# WX0_011_104DL.net
KiCad netlist of a schematic drawn in Altium Designer
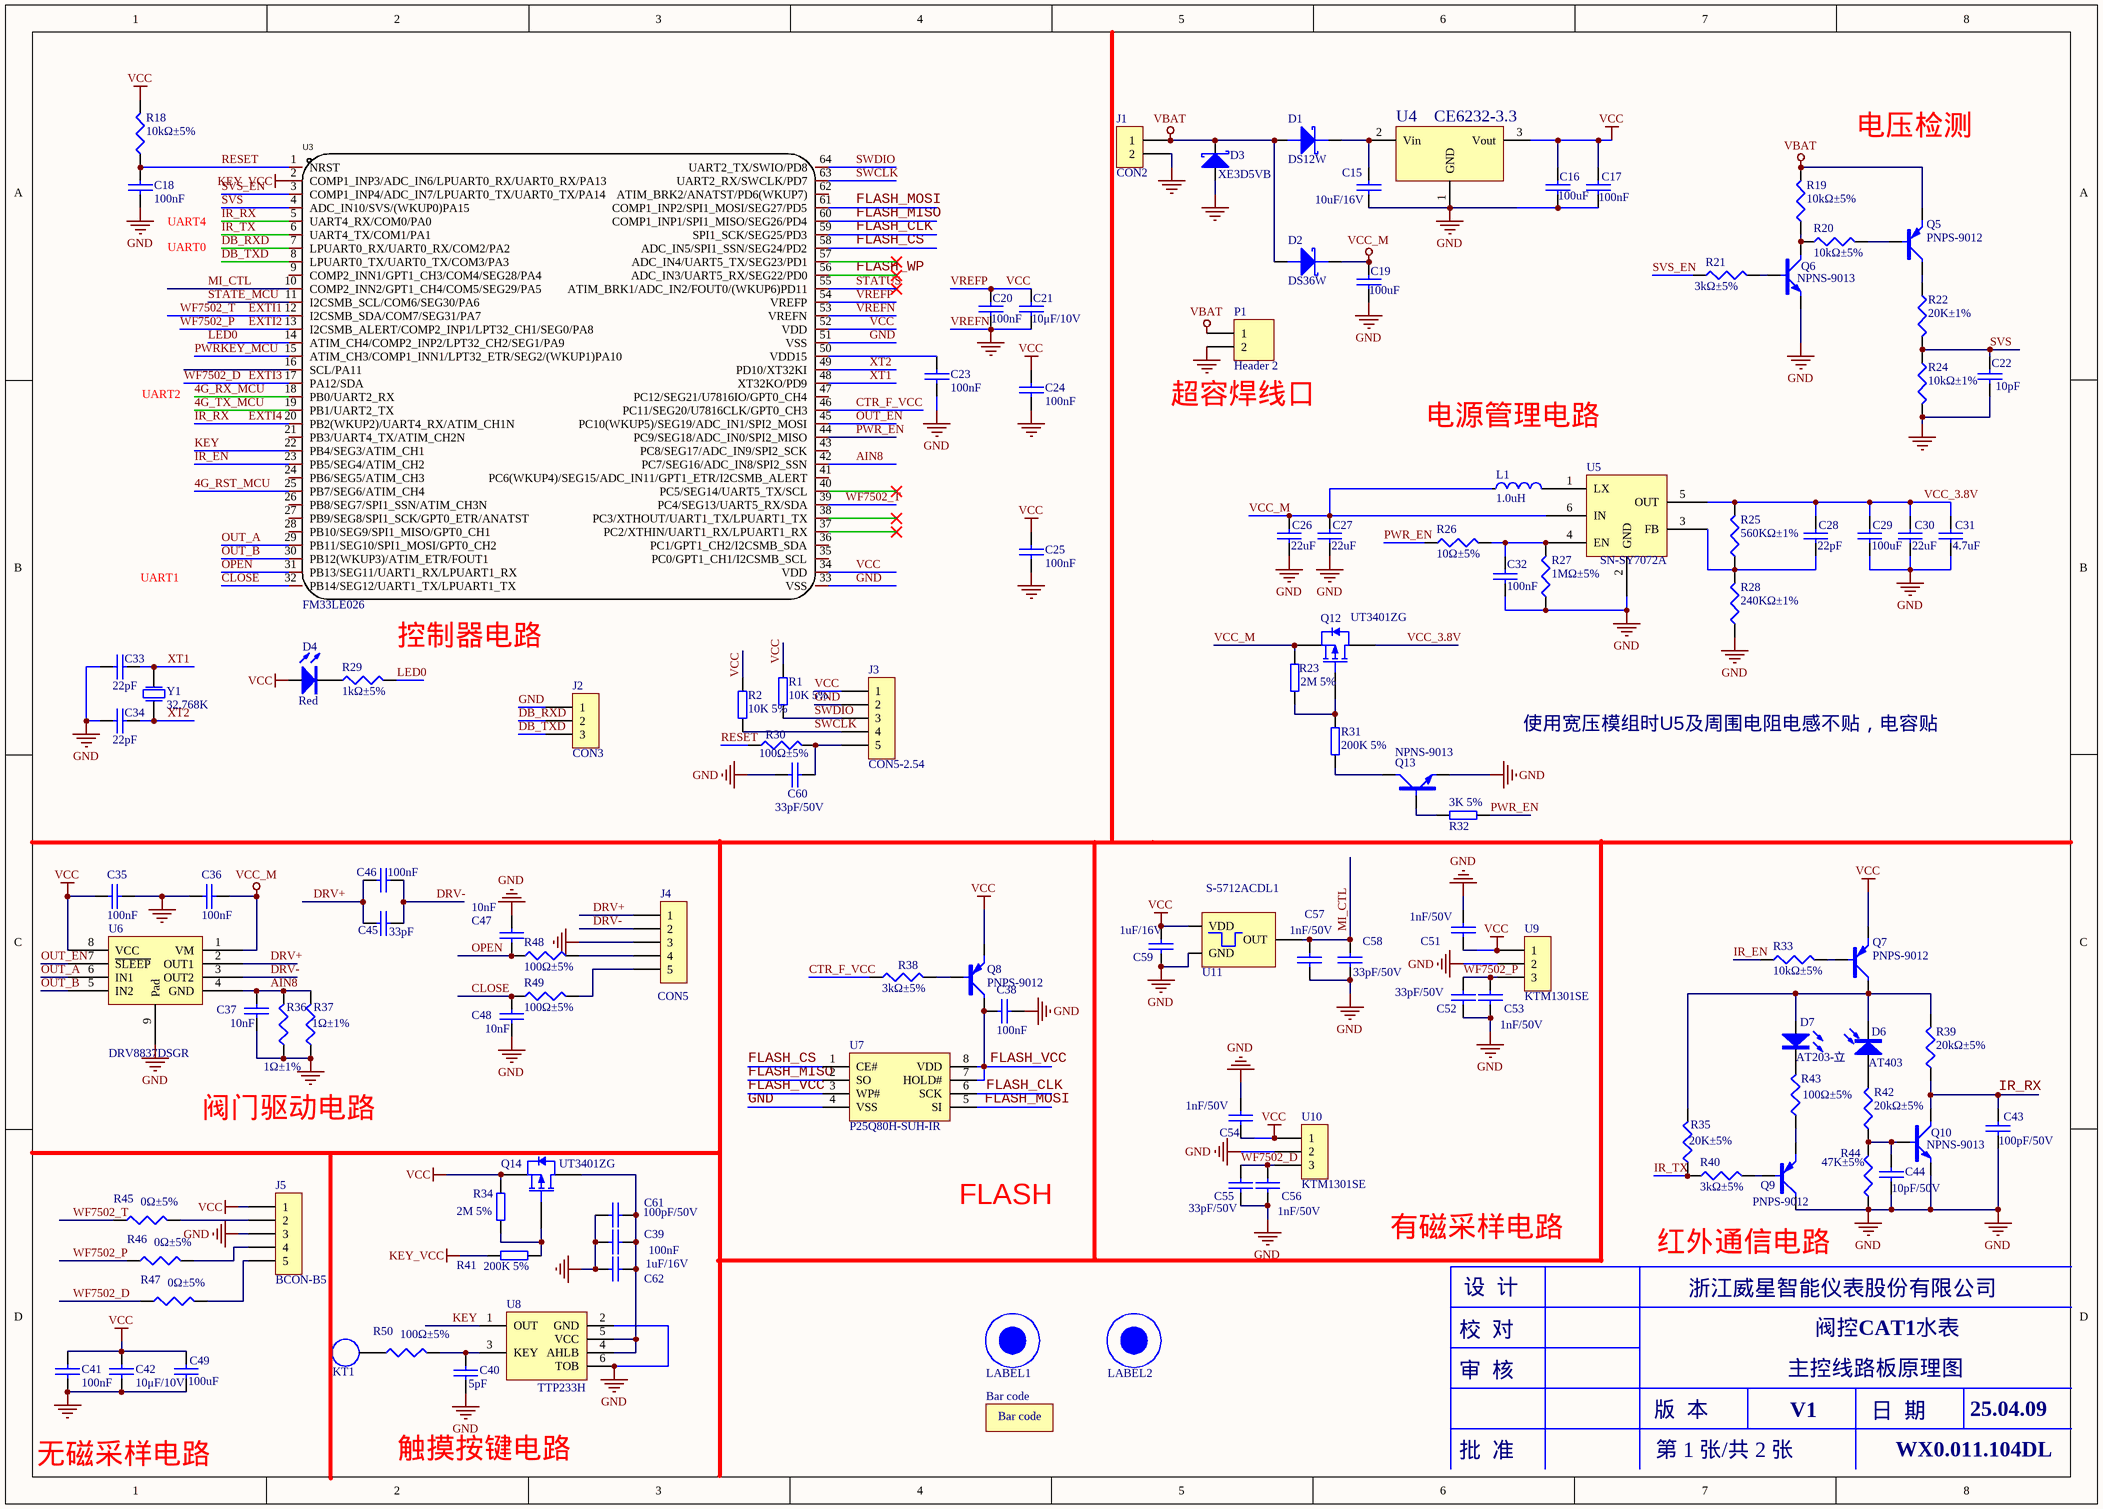
[diagram p0: WX0.011.104DL.SchDoc]

(export (version "E")
  (design (tool "Eeschema 10.0.6"))
  (components
    (comp (ref "Bar code")
      (value "Bar code")
      (footprint "Bar Code1")
      (libsource (lib "Connect_WX") (part "txm"))
    )
    (comp (ref "C15")
      (value "10uF/16V")
      (footprint "CAP0603")
      (description "105pF,16V,±10%,0603,国巨,CC0603KRX7R7BB105")
      (fields (field (name "PART NUMBER") "101020103-0003"))
      (libsource (lib "海外直通表U-GR3_GPRS") (part "CC03K7R7_1uF"))
    )
    (comp (ref "C16")
      (value "100uF")
      (footprint "GRM1206")
      (description "贴片电容,100uF±20%/6.3V,X5R,村田")
      (fields (field (name "PART NUMBER") "101020101-0020") (field (name "MANUFACTURER") "村田"))
      (libsource (lib "Devices") (part "CAP"))
    )
    (comp (ref "C17")
      (value "100nF")
      (footprint "CAP0603")
      (description "贴片电容,100nF±10%/50V,X7R,国巨")
      (fields (field (name "PART NUMBER") "101020103-0021") (field (name "MANUFACTURER") "国巨"))
      (libsource (lib "Devices") (part "CAP"))
    )
    (comp (ref "C18")
      (value "100nF")
      (footprint "CAP0603")
      (description "贴片电容,100nF±10%/50V,X7R,国巨")
      (fields (field (name "PART NUMBER") "101020103-0021") (field (name "MANUFACTURER") "国巨"))
      (libsource (lib "Devices") (part "CAP"))
    )
    (comp (ref "C19")
      (value "100uF")
      (footprint "GRM1206")
      (description "贴片电容,100uF±20%/6.3V,X5R,村田")
      (fields (field (name "PART NUMBER") "101020101-0020") (field (name "MANUFACTURER") "村田"))
      (libsource (lib "Devices") (part "CAP"))
    )
    (comp (ref "C20")
      (value "100nF")
      (footprint "CAP0603")
      (description "贴片电容,100nF±10%/50V,X7R,国巨")
      (fields (field (name "PART NUMBER") "101020103-0021") (field (name "MANUFACTURER") "国巨"))
      (libsource (lib "Devices") (part "CAP"))
    )
    (comp (ref "C21")
      (value "10μF/10V")
      (footprint "CAP0603")
      (description "贴片电容,10μF±10%/10V,X7R,村田")
      (fields (field (name "PART NUMBER") "101020103-0026") (field (name "MANUFACTURER") "村田"))
      (libsource (lib "Devices") (part "CAP"))
    )
    (comp (ref "C22")
      (value "10pF")
      (footprint "CAP0603")
      (description "贴片电容,12pF±5%/50V,NPO,国巨")
      (fields (field (name "PART NUMBER") "101020103-0005") (field (name "MANUFACTURER") "国巨"))
      (libsource (lib "Devices") (part "CAP"))
    )
    (comp (ref "C23")
      (value "100nF")
      (footprint "CAP0603")
      (description "贴片电容,100nF±10%/50V,X7R,国巨")
      (fields (field (name "PART NUMBER") "101020103-0021") (field (name "MANUFACTURER") "国巨"))
      (libsource (lib "Devices") (part "CAP"))
    )
    (comp (ref "C24")
      (value "100nF")
      (footprint "CAP0603")
      (description "贴片电容,100nF±10%/50V,X7R,国巨")
      (fields (field (name "PART NUMBER") "101020103-0021") (field (name "MANUFACTURER") "国巨"))
      (libsource (lib "Devices") (part "CAP"))
    )
    (comp (ref "C25")
      (value "100nF")
      (footprint "CAP0603")
      (description "贴片电容,100nF±10%/50V,X7R,国巨")
      (fields (field (name "PART NUMBER") "101020103-0021") (field (name "MANUFACTURER") "国巨"))
      (libsource (lib "Devices") (part "CAP"))
    )
    (comp (ref "C26")
      (value "22uF")
      (footprint "CAP0603")
      (description "贴片电容,22uF±20%,10V,X5R,村田")
      (fields (field (name "PART NUMBER") "101020103-0037") (field (name "MANUFACTURER") "村田"))
      (libsource (lib "Devices") (part "CAP"))
    )
    (comp (ref "C27")
      (value "22uF")
      (footprint "CAP0603")
      (description "贴片电容,22uF±20%,10V,X5R,村田")
      (fields (field (name "PART NUMBER") "101020103-0037") (field (name "MANUFACTURER") "村田"))
      (libsource (lib "Devices") (part "CAP"))
    )
    (comp (ref "C28")
      (value "22pF")
      (footprint "CAP0603")
      (description "贴片电容,22pF±5%/50V,NP0,国巨")
      (fields (field (name "PART NUMBER") "101020103-0009") (field (name "MANUFACTURER") "国巨"))
      (libsource (lib "Devices") (part "CAP"))
    )
    (comp (ref "C29")
      (value "100uF")
      (footprint "GRM1206")
      (description "贴片电容,100uF±20%/6.3V,X5R,村田")
      (fields (field (name "PART NUMBER") "101020101-0020") (field (name "MANUFACTURER") "村田"))
      (libsource (lib "Devices") (part "CAP"))
    )
    (comp (ref "C30")
      (value "22uF")
      (footprint "CAP0603")
      (description "贴片电容,22uF±20%,10V,X5R,村田")
      (fields (field (name "PART NUMBER") "101020103-0037") (field (name "MANUFACTURER") "村田"))
      (libsource (lib "Devices") (part "CAP"))
    )
    (comp (ref "C31")
      (value "4.7uF")
      (footprint "CAP0603")
      (description "贴片电容,4.7uF±10%/35V,X5R,村田")
      (fields (field (name "PART NUMBER") "101020103-0036") (field (name "MANUFACTURER") "村田"))
      (libsource (lib "Devices") (part "CAP"))
    )
    (comp (ref "C32")
      (value "100nF")
      (footprint "CAP0603")
      (description "贴片电容,100nF±10%/50V,X7R,国巨")
      (fields (field (name "PART NUMBER") "101020103-0021") (field (name "MANUFACTURER") "国巨"))
      (libsource (lib "Devices") (part "CAP"))
    )
    (comp (ref "C33")
      (value "22pF")
      (footprint "CAP0603")
      (description "贴片电容,22pF±5%/50V,NP0,国巨")
      (fields (field (name "PART NUMBER") "101020103-0009") (field (name "MANUFACTURER") "国巨"))
      (libsource (lib "Devices") (part "CAP"))
    )
    (comp (ref "C34")
      (value "22pF")
      (footprint "CAP0603")
      (description "贴片电容,22pF±5%/50V,NP0,国巨")
      (fields (field (name "PART NUMBER") "101020103-0009") (field (name "MANUFACTURER") "国巨"))
      (libsource (lib "Devices") (part "CAP"))
    )
    (comp (ref "C35")
      (value "100nF")
      (footprint "CAP0603")
      (description "贴片电容,100nF±10%/50V,X7R,国巨")
      (fields (field (name "PART NUMBER") "101020103-0021") (field (name "MANUFACTURER") "国巨"))
      (libsource (lib "Devices") (part "CAP"))
    )
    (comp (ref "C36")
      (value "100nF")
      (footprint "CAP0603")
      (description "贴片电容,100nF±10%/50V,X7R,国巨")
      (fields (field (name "PART NUMBER") "101020103-0021") (field (name "MANUFACTURER") "国巨"))
      (libsource (lib "Devices") (part "CAP"))
    )
    (comp (ref "C37")
      (value "10nF")
      (footprint "CAP0603")
      (description "贴片电容,10nF±10%/50V,X7R,国巨")
      (fields (field (name "PART NUMBER") "101020103-0007") (field (name "MANUFACTURER") "国巨"))
      (libsource (lib "Devices") (part "CAP"))
    )
    (comp (ref "C38")
      (value "100nF")
      (footprint "CAP0603")
      (description "贴片电容,100nF±10%/50V,X7R,国巨")
      (fields (field (name "PART NUMBER") "101020103-0021") (field (name "MANUFACTURER") "国巨"))
      (libsource (lib "Devices") (part "CAP"))
    )
    (comp (ref "C39")
      (value "100nF")
      (footprint "CAP0603")
      (description "贴片电容,100nF±10%/50V,X7R,国巨")
      (fields (field (name "PART NUMBER") "101020103-0021") (field (name "MANUFACTURER") "国巨"))
      (libsource (lib "Devices") (part "CAP"))
    )
    (comp (ref "C40")
      (value "5pF")
      (footprint "CAP0603")
      (description "贴片电容,4.7pF±0.25pF/50V,NPO,国巨")
      (fields (field (name "PART NUMBER") "101020103-0040") (field (name "MANUFACTURER") "国巨"))
      (libsource (lib "Devices") (part "CAP"))
    )
    (comp (ref "C41")
      (value "100nF")
      (footprint "CAP0603")
      (description "贴片电容,100nF±10%/50V,X7R,国巨")
      (fields (field (name "PART NUMBER") "101020103-0021") (field (name "MANUFACTURER") "国巨"))
      (libsource (lib "Devices") (part "CAP"))
    )
    (comp (ref "C42")
      (value "10μF/10V")
      (footprint "CAP0603")
      (description "贴片电容,1μF±10%/16V,X7R,国巨")
      (fields (field (name "PART NUMBER") "101020103-0003") (field (name "MANUFACTURER") "国巨"))
      (libsource (lib "Devices") (part "CAP"))
    )
    (comp (ref "C43")
      (value "100pF/50V")
      (footprint "CAP0603")
      (description "101pf,50 V,±5%,0603,国巨,CC0603JRNP09BN101")
      (fields (field (name "PART NUMBER") "101020103-0010"))
      (libsource (lib "Database_Libs2") (part "CC03JPO9_101P"))
    )
    (comp (ref "C44")
      (value "10pF/50V")
      (footprint "CAP0603")
      (description "10pF,50 V,±5%,0603,X7R,国巨,CC0603JRNPO9BN100")
      (fields (field (name "PART NUMBER") "101020103-0014"))
      (libsource (lib "Database_Libs2") (part "CC03JPO9_10P"))
    )
    (comp (ref "C45")
      (value "33pF")
      (footprint "CAP0603")
      (description "贴片电容,100nF±10%/50V,X7R,国巨")
      (fields (field (name "PART NUMBER") "101020103-0021") (field (name "MANUFACTURER") "国巨"))
      (libsource (lib "Devices") (part "CAP"))
    )
    (comp (ref "C46")
      (value "100nF")
      (footprint "CAP0603")
      (description "贴片电容,100nF±10%/50V,X7R,国巨")
      (fields (field (name "PART NUMBER") "101020103-0021") (field (name "MANUFACTURER") "国巨"))
      (libsource (lib "Devices") (part "CAP"))
    )
    (comp (ref "C47")
      (value "10nF")
      (footprint "CAP0603")
      (description "贴片电容,10nF±10%/50V,X7R,国巨")
      (fields (field (name "PART NUMBER") "101020103-0007") (field (name "MANUFACTURER") "国巨"))
      (libsource (lib "Devices") (part "CAP"))
    )
    (comp (ref "C48")
      (value "10nF")
      (footprint "CAP0603")
      (description "贴片电容,10nF±10%/50V,X7R,国巨")
      (fields (field (name "PART NUMBER") "101020103-0007") (field (name "MANUFACTURER") "国巨"))
      (libsource (lib "Devices") (part "CAP"))
    )
    (comp (ref "C49")
      (value "100uF")
      (footprint "GRM1206")
      (description "贴片电容,100uF±20%/6.3V,X5R,村田")
      (fields (field (name "PART NUMBER") "101020101-0020") (field (name "MANUFACTURER") "村田"))
      (libsource (lib "Devices") (part "CAP"))
    )
    (comp (ref "C51")
      (value "1nF/50V")
      (footprint "CAP0603")
      (description "102pF,50 V,±10%,0603,国巨,CC0603KRX7R9BB102")
      (fields (field (name "PART NUMBER") "101020103-0022"))
      (libsource (lib "Database_Libs2") (part "CC03K7R9_1N"))
    )
    (comp (ref "C52")
      (value "33pF/50V")
      (footprint "CAP0603")
      (description "33pF,50 V,±10%,0603,国巨,CC0603KRNPO9BN33")
      (fields (field (name "PART NUMBER") "101020103-0027"))
      (libsource (lib "Database_Libs2") (part "CC03KPO9_33P"))
    )
    (comp (ref "C53")
      (value "1nF/50V")
      (footprint "CAP0603")
      (description "102pF,50 V,±10%,0603,国巨,CC0603KRX7R9BB102")
      (fields (field (name "PART NUMBER") "101020103-0022"))
      (libsource (lib "Database_Libs2") (part "CC03K7R9_1N"))
    )
    (comp (ref "C54")
      (value "1nF/50V")
      (footprint "CAP0603")
      (description "102pF,50 V,±10%,0603,国巨,CC0603KRX7R9BB102")
      (fields (field (name "PART NUMBER") "101020103-0022"))
      (libsource (lib "Database_Libs2") (part "CC03K7R9_1N"))
    )
    (comp (ref "C55")
      (value "33pF/50V")
      (footprint "CAP0603")
      (description "33pF,50 V,±10%,0603,国巨,CC0603KRNPO9BN33")
      (fields (field (name "PART NUMBER") "101020103-0027"))
      (libsource (lib "Database_Libs2") (part "CC03KPO9_33P"))
    )
    (comp (ref "C56")
      (value "1nF/50V")
      (footprint "CAP0603")
      (description "102pF,50 V,±10%,0603,国巨,CC0603KRX7R9BB102")
      (fields (field (name "PART NUMBER") "101020103-0022"))
      (libsource (lib "Database_Libs2") (part "CC03K7R9_1N"))
    )
    (comp (ref "C57")
      (value "1nF/50V")
      (footprint "CAP0603")
      (description "102pF,50 V,±10%,0603,国巨,CC0603KRX7R9BB102")
      (fields (field (name "PART NUMBER") "101020103-0022"))
      (libsource (lib "Database_Libs2") (part "CC03K7R9_1N"))
    )
    (comp (ref "C58")
      (value "33pF/50V")
      (footprint "CAP0603")
      (description "33pF,50 V,±10%,0603,国巨,CC0603KRNPO9BN33")
      (fields (field (name "PART NUMBER") "101020103-0027"))
      (libsource (lib "Database_Libs2") (part "CC03KPO9_33P"))
    )
    (comp (ref "C59")
      (value "1uF/16V")
      (footprint "CAP0603")
      (description "105pF,16 V,±10%,0603,国巨,CC0603KRX7R7BB105")
      (fields (field (name "PART NUMBER") "101020103-0003"))
      (libsource (lib "Database_Libs2") (part "CC03K7R7_1U"))
    )
    (comp (ref "C60")
      (value "33pF/50V")
      (footprint "CAP0603")
      (description "33pF,50 V,±10%,0603,国巨,CC0603KRNPO9BN33")
      (fields (field (name "PART NUMBER") "101020103-0027"))
      (libsource (lib "Database_Libs2") (part "CC03KPO9_33P"))
    )
    (comp (ref "C61")
      (value "100pF/50V")
      (footprint "CAP0603")
      (description "101pf,50 V,±5%,0603,国巨,CC0603JRNP09BN101")
      (fields (field (name "PART NUMBER") "101020103-0010"))
      (libsource (lib "Database_Libs2") (part "CC03JPO9_101P"))
    )
    (comp (ref "C62")
      (value "1uF/16V")
      (footprint "CAP0603")
      (description "105pF,16 V,±10%,0603,国巨,CC0603KRX7R7BB105")
      (fields (field (name "PART NUMBER") "101020103-0003"))
      (libsource (lib "Database_Libs2") (part "CC03K7R7_1U"))
    )
    (comp (ref "D1")
      (value "DS12W")
      (footprint "SOD-123FL")
      (description "DS36W,SOD123-FL,3 A,42 V,60 V,浙江领晨科技有限公司,DS36W")
      (fields (field (name "PART NUMBER") "101040101-0055"))
      (libsource (lib "Database_Libs2") (part "02_DS36W"))
    )
    (comp (ref "D2")
      (value "DS36W")
      (footprint "SOD-123FL")
      (description "DS36W,SOD123-FL,3 A,42 V,60 V,浙江领晨科技有限公司,DS36W")
      (fields (field (name "PART NUMBER") "101040101-0055"))
      (libsource (lib "Database_Libs2") (part "02_DS36W"))
    )
    (comp (ref "D3")
      (value "XE3D5VB")
      (footprint "SOD-323_L1.8-W1.3-LS2.5-RD")
      (description "具有3.5pF低结电容，适用于IO线、电源线、高速信号的ESD二极管阵列,SOD-323,5 V,5 V,350 W,5 A,1 uA,矽航,XE3D5VB")
      (fields (field (name "PART NUMBER") "101040104-0010") (field (name "MANUFACTURER") "矽航"))
      (libsource (lib "Devices") (part "DIODE1"))
    )
    (comp (ref "D4")
      (value "Red")
      (footprint "LED-0603")
      (description "发光二极管,红色,0603,光宝")
      (fields (field (name "PART NUMBER") "101040102-0006") (field (name "MANUFACTURER") "光宝"))
      (libsource (lib "") (part "LED_1"))
    )
    (comp (ref "D6")
      (value "AT403")
      (footprint "LED2_300")
      (description "红外接收头，插件，红光，AT403_PD_01")
      (fields (field (name "PART NUMBER") "101040102-0011") (field (name "MANUFACTURER") "品观"))
      (libsource (lib "Devices") (part "LED_IN"))
    )
    (comp (ref "D7")
      (value "AT203-立")
      (footprint "LED2_300")
      (description "红外发射头，插件，红光，AT203")
      (fields (field (name "PART NUMBER") "101040102-0010") (field (name "MANUFACTURER") "品观"))
      (libsource (lib "Devices") (part "LED"))
    )
    (comp (ref "J1")
      (value "CON2")
      (footprint "SIP-2")
      (description "焊接插座,间距2.54mm")
      (libsource (lib "Devices") (part "CON2"))
    )
    (comp (ref "J2")
      (value "CON3")
      (footprint "SIP-3")
      (description "焊接插座,间距2.54mm")
      (libsource (lib "Devices") (part "CON3"))
    )
    (comp (ref "J3")
      (value "CON5-2.54")
      (footprint "PIN254_1*5*1100S")
      (description "焊接插座,间距2.0mm")
      (libsource (lib "Devices") (part "CON5"))
    )
    (comp (ref "J4")
      (value "CON5")
      (footprint "PIN254_1*5*1100S")
      (description "焊接插座,间距2.54mm")
      (libsource (lib "Devices") (part "CON5"))
    )
    (comp (ref "J5")
      (value "BCON-B5")
      (footprint "J_DIP_2.0_1*05_H")
      (description "焊接插座,90度插板双面焊盘,公头,间距1.5mm")
      (libsource (lib "Devices") (part "CON5"))
    )
    (comp (ref "KT1")
      (value "Touch")
      (footprint "TOUCH-1")
      (description "按键,6mm弹簧按键,按键直径10mm")
      (fields (field (name "PART NUMBER") "1011001-0060"))
      (libsource (lib "Devices") (part "TOUCHKEY"))
    )
    (comp (ref "L1")
      (value "1.0uH")
      (footprint "IND-SMD_L3.0-W3.0")
      (description "电感，1.0uH,2.7A,±20%,3.3*1.5mm，74438335010，伍尔特电子有限公司")
      (fields (field (name "PART NUMBER") "1010302-0019"))
      (libsource (lib "Devices") (part "L"))
    )
    (comp (ref "LABEL1")
      (value "~")
      (footprint "MARK")
      (description "标准Mark点,直径1mm,阻焊开窗3mm")
      (libsource (lib "Devices") (part "MARK"))
    )
    (comp (ref "LABEL2")
      (value "~")
      (footprint "MARK")
      (description "标准Mark点,直径1mm,阻焊开窗3mm")
      (libsource (lib "Devices") (part "MARK"))
    )
    (comp (ref "P1") (value "Header 2") (footprint "SIP-2") (libsource (lib "Connect_WX") (part "Header 2")))
    (comp (ref "Q5")
      (value "PNPS-9012")
      (footprint "SOT-23")
      (description "9012,PNP,SOT-23,JCET;长电,S9012")
      (fields (field (name "PART NUMBER") "101040201-0001"))
      (libsource (lib "Database_Libs2") (part "03_PNPS-9012"))
    )
    (comp (ref "Q6")
      (value "NPNS-9013")
      (footprint "SOT-23")
      (description "9013,NPN,SOT-23,长电,S9013")
      (fields (field (name "PART NUMBER") "101040201-0002"))
      (libsource (lib "Database_Libs2") (part "03_NPNS-9013"))
    )
    (comp (ref "Q7")
      (value "PNPS-9012")
      (footprint "SOT-23")
      (description "9012,PNP,SOT-23,JCET;长电,S9012")
      (fields (field (name "PART NUMBER") "101040201-0001"))
      (libsource (lib "Database_Libs2") (part "03_PNPS-9012"))
    )
    (comp (ref "Q8")
      (value "PNPS-9012")
      (footprint "SOT-23")
      (description "9012,PNP,SOT-23,JCET;长电,S9012")
      (fields (field (name "PART NUMBER") "101040201-0001"))
      (libsource (lib "Database_Libs2") (part "03_PNPS-9012"))
    )
    (comp (ref "Q9")
      (value "PNPS-9012")
      (footprint "SOT-23")
      (description "9012,PNP,SOT-23,JCET;长电,S9012")
      (fields (field (name "PART NUMBER") "101040201-0001"))
      (libsource (lib "Database_Libs2") (part "03_PNPS-9012"))
    )
    (comp (ref "Q10")
      (value "NPNS-9013")
      (footprint "SOT-23")
      (description "9013,NPN,SOT-23,长电,S9013")
      (fields (field (name "PART NUMBER") "101040201-0002"))
      (libsource (lib "Database_Libs2") (part "03_NPNS-9013"))
    )
    (comp (ref "Q12")
      (value "UT3401ZG")
      (footprint "SOT-23")
      (description "UT3401ZG,P-MOS,SOT-23,UTC,UT3401ZG")
      (fields (field (name "PART NUMBER") "101040201-0013"))
      (libsource (lib "Database_Libs2") (part "03_P-UT3401ZG"))
    )
    (comp (ref "Q13")
      (value "NPNS-9013")
      (footprint "SOT-23")
      (description "9013,NPN,SOT-23,长电,S9013")
      (fields (field (name "PART NUMBER") "101040201-0002"))
      (libsource (lib "Database_Libs2") (part "03_NPNS-9013"))
    )
    (comp (ref "Q14")
      (value "UT3401ZG")
      (footprint "SOT-23")
      (description "UT3401ZG,P-MOS,SOT-23,UTC,UT3401ZG")
      (fields (field (name "PART NUMBER") "101040201-0013"))
      (libsource (lib "Database_Libs2") (part "03_P-UT3401ZG"))
    )
    (comp (ref "R1")
      (value "10K 5%")
      (footprint "RES0603")
      (description "国巨,±5%,0603,,155 ℃,-55 ℃,RC0603JR-0710KL,无铅,200 ppm/℃,1/10W,,10K")
      (fields (field (name "PART NUMBER") "101010103-0003"))
      (libsource (lib "Database_Libs2") (part "RC03J_10K"))
    )
    (comp (ref "R2")
      (value "10K 5%")
      (footprint "RES0603")
      (description "国巨,±5%,0603,,155 ℃,-55 ℃,RC0603JR-0710KL,无铅,200 ppm/℃,1/10W,,10K")
      (fields (field (name "PART NUMBER") "101010103-0003"))
      (libsource (lib "Database_Libs2") (part "RC03J_10K"))
    )
    (comp (ref "R18")
      (value "10kΩ±5%")
      (footprint "RES0603")
      (description "贴片电阻,10kΩ±5%,1/10W,100ppm/℃,国巨")
      (fields (field (name "PART NUMBER") "101010103-0003") (field (name "MANUFACTURER") "国巨"))
      (libsource (lib "Devices") (part "RES1"))
    )
    (comp (ref "R19")
      (value "10kΩ±5%")
      (footprint "RES0603")
      (description "贴片电阻,10kΩ±5%,1/10W,100ppm/℃,国巨")
      (fields (field (name "PART NUMBER") "101010103-0003") (field (name "MANUFACTURER") "国巨"))
      (libsource (lib "Devices") (part "RES1"))
    )
    (comp (ref "R20")
      (value "10kΩ±5%")
      (footprint "RES0603")
      (description "贴片电阻,10kΩ±5%,1/10W,100ppm/℃,国巨")
      (fields (field (name "PART NUMBER") "101010103-0003") (field (name "MANUFACTURER") "国巨"))
      (libsource (lib "Devices") (part "RES1"))
    )
    (comp (ref "R21")
      (value "3kΩ±5%")
      (footprint "RES0603")
      (description "贴片电阻,4.7kΩ±5%,1/10W,100ppm/℃,国巨")
      (fields (field (name "PART NUMBER") "101010103-0042") (field (name "MANUFACTURER") "国巨"))
      (libsource (lib "Devices") (part "RES1"))
    )
    (comp (ref "R22")
      (value "20K±1%")
      (footprint "RES0603")
      (description "贴片电阻，20K,±1%,1/10W,0603,国巨,RC0603FR-0720KL")
      (fields (field (name "PART NUMBER") "101010103-0048") (field (name "MANUFACTURER") "国巨"))
      (libsource (lib "Devices") (part "RES1"))
    )
    (comp (ref "R23")
      (value "2M 5%")
      (footprint "RES0603")
      (description "国巨,±5%,0603,,155 ℃,-55 ℃,RC0603JR-072ML,含铅,100 ppm/℃,1/10W,,2M")
      (fields (field (name "PART NUMBER") "101010103-0025"))
      (libsource (lib "Database_Libs2") (part "RC03J_2M"))
    )
    (comp (ref "R24")
      (value "10kΩ±1%")
      (footprint "RES0603")
      (description "贴片电阻,10kΩ±1%,1/10W,100ppm/℃,国巨")
      (fields (field (name "PART NUMBER") "101010103-0052") (field (name "MANUFACTURER") "国巨"))
      (libsource (lib "Devices") (part "RES1"))
    )
    (comp (ref "R25")
      (value "560KΩ±1%")
      (footprint "RES0603")
      (description "贴片电阻，560KΩ±1%,0603,国巨，RC0603FR-07560KL")
      (fields (field (name "PART NUMBER") "101010103-0109") (field (name "MANUFACTURER") "国巨"))
      (libsource (lib "Devices") (part "RES1"))
    )
    (comp (ref "R26")
      (value "10Ω±5%")
      (footprint "RES0603")
      (description "贴片电阻,10Ω±5%,1/10W,100ppm/℃,国巨")
      (fields (field (name "PART NUMBER") "101010103-0017") (field (name "MANUFACTURER") "国巨"))
      (libsource (lib "Devices") (part "RES1"))
    )
    (comp (ref "R27")
      (value "1MΩ±5%")
      (footprint "RES0603")
      (description "贴片电阻,1MΩ±5%,1/10W,100ppm/℃,国巨")
      (fields (field (name "PART NUMBER") "101010103-0002") (field (name "MANUFACTURER") "国巨"))
      (libsource (lib "Devices") (part "RES1"))
    )
    (comp (ref "R28")
      (value "240KΩ±1%")
      (footprint "RES0603")
      (description "贴片电阻，240KΩ±1%,0603,国巨，RC0603FR-07240KL")
      (fields (field (name "PART NUMBER") "101010103-0105") (field (name "MANUFACTURER") "国巨"))
      (libsource (lib "Devices") (part "RES1"))
    )
    (comp (ref "R29")
      (value "1kΩ±5%")
      (footprint "RES0603")
      (description "贴片电阻,1kΩ±5%,1/10W,100ppm/℃,国巨")
      (fields (field (name "PART NUMBER") "101010103-0008") (field (name "MANUFACTURER") "国巨"))
      (libsource (lib "Devices") (part "RES1"))
    )
    (comp (ref "R30")
      (value "100Ω±5%")
      (footprint "RES0603")
      (description "贴片电阻,0Ω±5%,1/10W,100ppm/℃,国巨")
      (fields (field (name "PART NUMBER") "101010103-0001") (field (name "MANUFACTURER") "国巨"))
      (libsource (lib "Devices") (part "RES1"))
    )
    (comp (ref "R31")
      (value "200K 5%")
      (footprint "RES0603")
      (description "200K,±5%,1/10W,0603,国巨,RC0603JR-07200KL")
      (fields (field (name "PART NUMBER") "101010103-0034"))
      (libsource (lib "Database_Libs2") (part "RC03J_200K"))
    )
    (comp (ref "R32")
      (value "3K 5%")
      (footprint "RES0603")
      (description "国巨,±5%,0603,,155 ℃,-55 ℃,RC0603JR-073KL,无铅,100 ppm/℃,1/10W,,3K")
      (fields (field (name "PART NUMBER") "101010103-0006"))
      (libsource (lib "Database_Libs2") (part "RC03J_3K"))
    )
    (comp (ref "R33")
      (value "10kΩ±5%")
      (footprint "RES0603")
      (description "贴片电阻,1kΩ±5%,1/10W,100ppm/℃,国巨")
      (fields (field (name "PART NUMBER") "101010103-0008") (field (name "MANUFACTURER") "国巨"))
      (libsource (lib "Devices") (part "RES1"))
    )
    (comp (ref "R34")
      (value "2M 5%")
      (footprint "RES0603")
      (description "国巨,±5%,0603,,155 ℃,-55 ℃,RC0603JR-072ML,含铅,100 ppm/℃,1/10W,,2M")
      (fields (field (name "PART NUMBER") "101010103-0025"))
      (libsource (lib "Database_Libs2") (part "RC03J_2M"))
    )
    (comp (ref "R35")
      (value "20K±5%")
      (footprint "RES0603")
      (description "贴片电阻,1MΩ±5%,1/10W,100ppm/℃,国巨")
      (fields (field (name "PART NUMBER") "101010103-0002") (field (name "MANUFACTURER") "国巨"))
      (libsource (lib "Devices") (part "RES1"))
    )
    (comp (ref "R36")
      (value "1Ω±1%")
      (footprint "R1206")
      (description "贴片电阻，1Ω±1%,1/4W,1206,国巨,RC1206FR-071RL")
      (fields (field (name "PART NUMBER") "101010101-0034") (field (name "MANUFACTURER") "国巨"))
      (libsource (lib "Devices") (part "RES1"))
    )
    (comp (ref "R37")
      (value "1Ω±1%")
      (footprint "R1206")
      (description "贴片电阻，1Ω±1%,1/4W,1206,国巨,RC1206FR-071RL")
      (fields (field (name "PART NUMBER") "101010101-0034") (field (name "MANUFACTURER") "国巨"))
      (libsource (lib "Devices") (part "RES1"))
    )
    (comp (ref "R38")
      (value "3kΩ±5%")
      (footprint "RES0603")
      (description "贴片电阻,10kΩ±5%,1/10W,100ppm/℃,国巨")
      (fields (field (name "PART NUMBER") "101010103-0003") (field (name "MANUFACTURER") "国巨"))
      (libsource (lib "Devices") (part "RES1"))
    )
    (comp (ref "R39")
      (value "20kΩ±5%")
      (footprint "RES0603")
      (description "贴片电阻,100kΩ±5%,1/10W,100ppm/℃,国巨")
      (fields (field (name "PART NUMBER") "101010103-0005") (field (name "MANUFACTURER") "国巨"))
      (libsource (lib "Devices") (part "RES1"))
    )
    (comp (ref "R40")
      (value "3kΩ±5%")
      (footprint "RES0603")
      (description "贴片电阻,1kΩ±5%,1/10W,100ppm/℃,国巨")
      (fields (field (name "PART NUMBER") "101010103-0008") (field (name "MANUFACTURER") "国巨"))
      (libsource (lib "Devices") (part "RES1"))
    )
    (comp (ref "R41")
      (value "200K 5%")
      (footprint "RES0603")
      (description "200K,±5%,1/10W,0603,国巨,RC0603JR-07200KL")
      (fields (field (name "PART NUMBER") "101010103-0034"))
      (libsource (lib "Database_Libs2") (part "RC03J_200K"))
    )
    (comp (ref "R42")
      (value "20kΩ±5%")
      (footprint "RES0603")
      (description "贴片电阻,20kΩ±5%,1/10W,100ppm/℃,国巨")
      (fields (field (name "PART NUMBER") "101010103-0004") (field (name "MANUFACTURER") "国巨"))
      (libsource (lib "Devices") (part "RES1"))
    )
    (comp (ref "R43")
      (value "100Ω±5%")
      (footprint "RES0603")
      (description "贴片电阻,100Ω±5%,1/10W,100ppm/℃,国巨")
      (fields (field (name "PART NUMBER") "101010103-0022") (field (name "MANUFACTURER") "国巨"))
      (libsource (lib "Devices") (part "RES1"))
    )
    (comp (ref "R44")
      (value "47K±5%")
      (footprint "RES0603")
      (description "贴片电阻，47K,±5%,1/10W,0603,国巨,RC0603JR-0747KL")
      (fields (field (name "PART NUMBER") "101010103-0012") (field (name "MANUFACTURER") "国巨"))
      (libsource (lib "Devices") (part "RES1"))
    )
    (comp (ref "R45")
      (value "0Ω±5%")
      (footprint "RES0603")
      (description "贴片电阻,100Ω±5%,1/10W,100ppm/℃,国巨")
      (fields (field (name "PART NUMBER") "101010103-0022") (field (name "MANUFACTURER") "国巨"))
      (libsource (lib "Devices") (part "RES1"))
    )
    (comp (ref "R46")
      (value "0Ω±5%")
      (footprint "RES0603")
      (description "贴片电阻,100Ω±5%,1/10W,100ppm/℃,国巨")
      (fields (field (name "PART NUMBER") "101010103-0022") (field (name "MANUFACTURER") "国巨"))
      (libsource (lib "Devices") (part "RES1"))
    )
    (comp (ref "R47")
      (value "0Ω±5%")
      (footprint "RES0603")
      (description "贴片电阻,100Ω±5%,1/10W,100ppm/℃,国巨")
      (fields (field (name "PART NUMBER") "101010103-0022") (field (name "MANUFACTURER") "国巨"))
      (libsource (lib "Devices") (part "RES1"))
    )
    (comp (ref "R48")
      (value "100Ω±5%")
      (footprint "RES0603")
      (description "贴片电阻,100Ω±5%,1/10W,100ppm/℃,国巨")
      (fields (field (name "PART NUMBER") "101010103-0022") (field (name "MANUFACTURER") "国巨"))
      (libsource (lib "Devices") (part "RES1"))
    )
    (comp (ref "R49")
      (value "100Ω±5%")
      (footprint "RES0603")
      (description "贴片电阻,100Ω±5%,1/10W,100ppm/℃,国巨")
      (fields (field (name "PART NUMBER") "101010103-0022") (field (name "MANUFACTURER") "国巨"))
      (libsource (lib "Devices") (part "RES1"))
    )
    (comp (ref "R50")
      (value "100Ω±5%")
      (footprint "RES0603")
      (description "贴片电阻,100Ω±5%,1/10W,100ppm/℃,国巨")
      (fields (field (name "PART NUMBER") "101010103-0022") (field (name "MANUFACTURER") "国巨"))
      (libsource (lib "Devices") (part "RES1"))
    )
    (comp (ref "U3")
      (value "FM33LE026")
      (footprint "LQFP-64_L10.0-W10.0-P0.50-LS12.0-BL")
      (description "单片机,FM33LE026,复旦微")
      (fields (field (name "MANUFACTURER") "复旦微") (field (name "MANUFACTURER PART") "FM33LC026N"))
      (libsource (lib "Devices") (part "FM33LE026"))
    )
    (comp (ref "U4")
      (value "CE6232-3.3")
      (footprint "SOT-89")
      (description "CE6232-3.3,CE6232-3.3,SOT89-3,8V,1.8V,0.11V,3.3V,300mA,0.8uA,南京芯力微电子有限公司")
      (fields (field (name "PART NUMBER") "1010503-0029"))
      (libsource (lib "海外直通表U-GR3_GPRS") (part "02_CE6232-3.3"))
    )
    (comp (ref "U5")
      (value "SN-SY7072A")
      (footprint "SOT-23-6")
      (description "集成电路，矽力杰股份有限公司，SN-SY7072A")
      (fields (field (name "PART NUMBER") "1010503-0023") (field (name "MANUFACTURER") "矽力杰股份有限公司"))
      (libsource (lib "Devices") (part "SN-SY7072A"))
    )
    (comp (ref "U6")
      (value "DRV8837DSGR")
      (footprint "S-PWSON-N8")
      (description "DRV8837DSGR,S-PWSON-N8,TI,DRV8837DSGR")
      (fields (field (name "PART NUMBER") "101050101-0060"))
      (libsource (lib "海外直通表U-GR3_GPRS") (part "07_DRV8837DSGR"))
    )
    (comp (ref "U7")
      (value "P25Q80H-SUH-IR")
      (footprint "SOP-8L-200MIL")
      (description "P25Q80H-SUH-IR,SOP8 208mil,普冉半导体（上海）股份有限公司,P25Q80H-SUH-IR")
      (fields (field (name "PART NUMBER") "101050101-0218"))
      (libsource (lib "海外直通表U-GR3_GPRS") (part "04_P25Q80H-SUH-IR"))
    )
    (comp (ref "U8")
      (value "TTP233H")
      (footprint "SOT-23-6")
      (description "集成电路，TTP233H,TONTEK")
      (fields (field (name "PART NUMBER") "101050101-0262") (field (name "MANUFACTURER") "TONTEK"))
      (libsource (lib "Devices") (part "TTP233H"))
    )
    (comp (ref "U9")
      (value "KTM1301SE")
      (footprint "ESP3_QYSW_JSZ")
      (description "昆泰KTM1301SE（插件）")
      (libsource (lib "Devices") (part "CON3"))
    )
    (comp (ref "U10")
      (value "KTM1301SE")
      (footprint "ESP3_QYSW_JSZ")
      (description "昆泰KTM1301SE（插件）")
      (libsource (lib "Devices") (part "CON3"))
    )
    (comp (ref "U11")
      (value "S-5712ACDL1")
      (footprint "SOT-23")
      (description "S-5712ACDL1,SOT23-3,3.5 V,1.6 V,2 uA,精工电子,S-5712ACDL1")
      (fields (field (name "PART NUMBER") "1010504-0002"))
      (libsource (lib "Database_Libs2") (part "01_S-5712ACDL1"))
    )
    (comp (ref "Y1")
      (value "32.768K")
      (footprint "SMD-3215_2P")
      (description "晶振,32.768KHz,±20ppm,12.5pF,3215,EPSON")
      (fields (field (name "PART NUMBER") "1010601-0009") (field (name "MANUFACTURER") "EPSON"))
      (libsource (lib "Devices") (part "XTAL"))
    )
  )
  (nets
    (net (code "1") (name "/4G_RST_MCU") (class "Default")
      (node (ref "U3") (pin "25") (pinfunction "PB7/SEG6/ATIM_CH4_25") (pintype "passive"))
    )
    (net (code "2") (name "/4G_RX_MCU") (class "Default")
      (node (ref "U3") (pin "18") (pinfunction "PB0/UART2_RX_18") (pintype "passive"))
    )
    (net (code "3") (name "/4G_TX_MCU") (class "Default")
      (node (ref "U3") (pin "19") (pinfunction "PB1/UART2_TX_19") (pintype "passive"))
    )
    (net (code "4") (name "/AIN8") (class "Default")
      (node (ref "C37") (pin "2") (pinfunction "2_2") (pintype "passive"))
      (node (ref "R36") (pin "2") (pinfunction "2_2") (pintype "passive"))
      (node (ref "R37") (pin "2") (pinfunction "2_2") (pintype "passive"))
      (node (ref "U3") (pin "42") (pinfunction "PC7/SEG16/ADC_IN8/SPI2_SSN_42") (pintype "passive"))
      (node (ref "U6") (pin "4") (pinfunction "GND_4") (pintype "passive"))
    )
    (net (code "5") (name "/CLOSE") (class "Default")
      (node (ref "C48") (pin "2") (pinfunction "2_2") (pintype "passive"))
      (node (ref "R49") (pin "1") (pinfunction "1_1") (pintype "passive"))
      (node (ref "U3") (pin "32") (pinfunction "PB14/SEG12/UART1_TX/LPUART1_TX_32") (pintype "passive"))
    )
    (net (code "6") (name "/CTR_F_VCC") (class "Default")
      (node (ref "R38") (pin "1") (pinfunction "1_1") (pintype "passive"))
      (node (ref "U3") (pin "46") (pinfunction "PC11/SEG20/U7816CLK/GPT0_CH3_46") (pintype "passive"))
    )
    (net (code "7") (name "/DB_RXD") (class "Default")
      (node (ref "J2") (pin "2") (pinfunction "2_2") (pintype "passive"))
      (node (ref "U3") (pin "7") (pinfunction "LPUART0_RX/UART0_RX/COM2/PA2_7") (pintype "passive"))
    )
    (net (code "8") (name "/DB_TXD") (class "Default")
      (node (ref "J2") (pin "3") (pinfunction "3_3") (pintype "passive"))
      (node (ref "U3") (pin "8") (pinfunction "LPUART0_TX/UART0_TX/COM3/PA3_8") (pintype "passive"))
    )
    (net (code "9") (name "/DRV+") (class "Default")
      (node (ref "C45") (pin "2") (pinfunction "2_2") (pintype "passive"))
      (node (ref "C46") (pin "2") (pinfunction "2_2") (pintype "passive"))
      (node (ref "J4") (pin "1") (pinfunction "1_1") (pintype "passive"))
      (node (ref "U6") (pin "2") (pinfunction "OUT1_2") (pintype "passive"))
    )
    (net (code "10") (name "/DRV-") (class "Default")
      (node (ref "C45") (pin "1") (pinfunction "1_1") (pintype "passive"))
      (node (ref "C46") (pin "1") (pinfunction "1_1") (pintype "passive"))
      (node (ref "J4") (pin "2") (pinfunction "2_2") (pintype "passive"))
      (node (ref "U6") (pin "3") (pinfunction "OUT2_3") (pintype "passive"))
    )
    (net (code "11") (name "/EXTI1") (class "Default")
      (node (ref "R45") (pin "1") (pinfunction "1_1") (pintype "passive"))
      (node (ref "U3") (pin "12") (pinfunction "I2CSMB_SDA/COM7/SEG31/PA7_12") (pintype "passive"))
      (node (ref "U3") (pin "39") (pinfunction "PC4/SEG13/UART5_RX/SDA_39") (pintype "passive"))
    )
    (net (code "12") (name "/EXTI2") (class "Default")
      (node (ref "C52") (pin "1") (pinfunction "1_1") (pintype "passive"))
      (node (ref "C53") (pin "1") (pinfunction "1_1") (pintype "passive"))
      (node (ref "R46") (pin "1") (pinfunction "1_1") (pintype "passive"))
      (node (ref "U3") (pin "13") (pinfunction "I2CSMB_ALERT/COMP2_INP1/LPT32_CH1/SEG0/PA8_13") (pintype "passive"))
      (node (ref "U9") (pin "3") (pinfunction "3_3") (pintype "passive"))
    )
    (net (code "13") (name "/EXTI3") (class "Default")
      (node (ref "C55") (pin "1") (pinfunction "1_1") (pintype "passive"))
      (node (ref "C56") (pin "1") (pinfunction "1_1") (pintype "passive"))
      (node (ref "R47") (pin "1") (pinfunction "1_1") (pintype "passive"))
      (node (ref "U10") (pin "3") (pinfunction "3_3") (pintype "passive"))
      (node (ref "U3") (pin "17") (pinfunction "PA12/SDA_17") (pintype "passive"))
    )
    (net (code "14") (name "/EXTI4") (class "Default")
      (node (ref "C43") (pin "1") (pinfunction "1_1") (pintype "passive"))
      (node (ref "Q10") (pin "3") (pinfunction "C_3") (pintype "passive"))
      (node (ref "R39") (pin "1") (pinfunction "1_1") (pintype "passive"))
      (node (ref "U3") (pin "20") (pinfunction "PB2(WKUP2)/UART4_RX/ATIM_CH1N_20") (pintype "passive"))
      (node (ref "U3") (pin "5") (pinfunction "UART4_RX/COM0/PA0_5") (pintype "passive"))
    )
    (net (code "15") (name "/FLASH_CLK") (class "Default")
      (node (ref "U3") (pin "59") (pinfunction "SPI1_SCK/SEG25/PD3_59") (pintype "passive"))
      (node (ref "U7") (pin "6") (pinfunction "SCK_6") (pintype "passive"))
    )
    (net (code "16") (name "/FLASH_CS") (class "Default")
      (node (ref "U3") (pin "58") (pinfunction "ADC_IN5/SPI1_SSN/SEG24/PD2_58") (pintype "passive"))
      (node (ref "U7") (pin "1") (pinfunction "CE#_1") (pintype "passive"))
    )
    (net (code "17") (name "/FLASH_MISO") (class "Default")
      (node (ref "U3") (pin "60") (pinfunction "COMP1_INP1/SPI1_MISO/SEG26/PD4_60") (pintype "passive"))
      (node (ref "U7") (pin "2") (pinfunction "SO_2") (pintype "passive"))
    )
    (net (code "18") (name "/FLASH_MOSI") (class "Default")
      (node (ref "U3") (pin "61") (pinfunction "COMP1_INP2/SPI1_MOSI/SEG27/PD5_61") (pintype "passive"))
      (node (ref "U7") (pin "5") (pinfunction "SI_5") (pintype "passive"))
    )
    (net (code "19") (name "/FLASH_VCC") (class "Default")
      (node (ref "C38") (pin "2") (pinfunction "2_2") (pintype "passive"))
      (node (ref "Q8") (pin "3") (pinfunction "C_3") (pintype "passive"))
      (node (ref "U7") (pin "3") (pinfunction "WP#_3") (pintype "passive"))
      (node (ref "U7") (pin "7") (pinfunction "HOLD#_7") (pintype "passive"))
      (node (ref "U7") (pin "8") (pinfunction "VDD_8") (pintype "passive"))
    )
    (net (code "20") (name "/FLASH_WP") (class "Default")
      (node (ref "U3") (pin "56") (pinfunction "ADC_IN3/UART5_RX/SEG22/PD0_56") (pintype "passive+no_connect"))
    )
    (net (code "21") (name "/IR_EN") (class "Default")
      (node (ref "R33") (pin "1") (pinfunction "1_1") (pintype "passive"))
      (node (ref "U3") (pin "23") (pinfunction "PB5/SEG4/ATIM_CH2_23") (pintype "passive"))
    )
    (net (code "22") (name "/IR_TX") (class "Default")
      (node (ref "R35") (pin "1") (pinfunction "1_1") (pintype "passive"))
      (node (ref "R40") (pin "1") (pinfunction "1_1") (pintype "passive"))
      (node (ref "U3") (pin "6") (pinfunction "UART4_TX/COM1/PA1_6") (pintype "passive"))
    )
    (net (code "23") (name "/KEY") (class "Default")
      (node (ref "U3") (pin "22") (pinfunction "PB4/SEG3/ATIM_CH1_22") (pintype "passive"))
      (node (ref "U8") (pin "1") (pinfunction "OUT_1") (pintype "passive"))
    )
    (net (code "24") (name "/LED0") (class "Default")
      (node (ref "R29") (pin "2") (pinfunction "2_2") (pintype "passive"))
      (node (ref "U3") (pin "14") (pinfunction "ATIM_CH4/COMP2_INP2/LPT32_CH2/SEG1/PA9_14") (pintype "passive"))
    )
    (net (code "25") (name "/MI_CTL") (class "Default")
      (node (ref "C57") (pin "1") (pinfunction "1_1") (pintype "passive"))
      (node (ref "C58") (pin "1") (pinfunction "1_1") (pintype "passive"))
      (node (ref "U11") (pin "2") (pinfunction "OUT_2") (pintype "passive"))
      (node (ref "U3") (pin "10") (pinfunction "COMP2_INN2/GPT1_CH4/COM5/SEG29/PA5_10") (pintype "passive"))
    )
    (net (code "26") (name "/OPEN") (class "Default")
      (node (ref "C47") (pin "1") (pinfunction "1_1") (pintype "passive"))
      (node (ref "R48") (pin "1") (pinfunction "1_1") (pintype "passive"))
      (node (ref "U3") (pin "31") (pinfunction "PB13/SEG11/UART1_RX/LPUART1_RX_31") (pintype "passive"))
    )
    (net (code "27") (name "/OUT_A") (class "Default")
      (node (ref "U3") (pin "29") (pinfunction "PB11/SEG10/SPI1_MOSI/GPT0_CH2_29") (pintype "passive"))
      (node (ref "U6") (pin "6") (pinfunction "IN1_6") (pintype "passive"))
    )
    (net (code "28") (name "/OUT_B") (class "Default")
      (node (ref "U3") (pin "30") (pinfunction "PB12(WKUP3)/ATIM_ETR/FOUT1_30") (pintype "passive"))
      (node (ref "U6") (pin "5") (pinfunction "IN2_5") (pintype "passive"))
    )
    (net (code "29") (name "/OUT_EN") (class "Default")
      (node (ref "U3") (pin "45") (pinfunction "PC10(WKUP5)/SEG19/ADC_IN1/SPI2_MOSI_45") (pintype "passive"))
      (node (ref "U6") (pin "7") (pinfunction "~{SLEEP}_7") (pintype "passive"))
    )
    (net (code "30") (name "/PWRKEY_MCU") (class "Default")
      (node (ref "U3") (pin "15") (pinfunction "ATIM_CH3/COMP1_INN1/LPT32_ETR/SEG2/(WKUP1)PA10_15") (pintype "passive"))
    )
    (net (code "31") (name "/PWR_EN") (class "Default")
      (node (ref "R26") (pin "1") (pinfunction "1_1") (pintype "passive"))
      (node (ref "R32") (pin "2") (pinfunction "2_2") (pintype "passive"))
      (node (ref "U3") (pin "44") (pinfunction "PC9/SEG18/ADC_IN0/SPI2_MISO_44") (pintype "passive"))
    )
    (net (code "32") (name "/RESET") (class "Default")
      (node (ref "C18") (pin "2") (pinfunction "2_2") (pintype "passive"))
      (node (ref "R18") (pin "1") (pinfunction "1_1") (pintype "passive"))
      (node (ref "R30") (pin "1") (pinfunction "1_1") (pintype "passive"))
      (node (ref "U3") (pin "1") (pinfunction "NRST_1") (pintype "passive"))
    )
    (net (code "33") (name "/STATE_MCU") (class "Default")
      (node (ref "U3") (pin "11") (pinfunction "I2CSMB_SCL/COM6/SEG30/PA6_11") (pintype "passive"))
    )
    (net (code "34") (name "/STATUS") (class "Default")
      (node (ref "U3") (pin "55") (pinfunction "ATIM_BRK1/ADC_IN2/FOUT0/(WKUP6)PD11_55") (pintype "passive+no_connect"))
    )
    (net (code "35") (name "/SVS") (class "Default")
      (node (ref "C22") (pin "2") (pinfunction "2_2") (pintype "passive"))
      (node (ref "R22") (pin "2") (pinfunction "2_2") (pintype "passive"))
      (node (ref "R24") (pin "1") (pinfunction "1_1") (pintype "passive"))
      (node (ref "U3") (pin "4") (pinfunction "ADC_IN10/SVS/(WKUP0)PA15_4") (pintype "passive"))
    )
    (net (code "36") (name "/SVS_EN") (class "Default")
      (node (ref "R21") (pin "1") (pinfunction "1_1") (pintype "passive"))
      (node (ref "U3") (pin "3") (pinfunction "COMP1_INP4/ADC_IN7/LPUART0_TX/UART0_TX/PA14_3") (pintype "passive"))
    )
    (net (code "37") (name "/SWCLK") (class "Default")
      (node (ref "J3") (pin "4") (pinfunction "4_4") (pintype "passive"))
      (node (ref "R2") (pin "1") (pinfunction "1_1") (pintype "passive"))
      (node (ref "U3") (pin "63") (pinfunction "UART2_RX/SWCLK/PD7_63") (pintype "passive"))
    )
    (net (code "38") (name "/SWDIO") (class "Default")
      (node (ref "J3") (pin "3") (pinfunction "3_3") (pintype "passive"))
      (node (ref "R1") (pin "1") (pinfunction "1_1") (pintype "passive"))
      (node (ref "U3") (pin "64") (pinfunction "UART2_TX/SWIO/PD8_64") (pintype "passive"))
    )
    (net (code "39") (name "/VCC_3.8V") (class "Default")
      (node (ref "C28") (pin "2") (pinfunction "2_2") (pintype "passive"))
      (node (ref "C29") (pin "2") (pinfunction "2_2") (pintype "passive"))
      (node (ref "C30") (pin "2") (pinfunction "2_2") (pintype "passive"))
      (node (ref "C31") (pin "2") (pinfunction "2_2") (pintype "passive"))
      (node (ref "Q12") (pin "3") (pinfunction "D_3") (pintype "passive"))
      (node (ref "R25") (pin "2") (pinfunction "2_2") (pintype "passive"))
      (node (ref "U5") (pin "5") (pinfunction "OUT_5") (pintype "passive"))
    )
    (net (code "40") (name "/XT1") (class "Default")
      (node (ref "C33") (pin "2") (pinfunction "2_2") (pintype "passive"))
      (node (ref "U3") (pin "48") (pinfunction "XT32KO/PD9_48") (pintype "passive"))
      (node (ref "Y1") (pin "2") (pinfunction "P2_2") (pintype "passive"))
    )
    (net (code "41") (name "/XT2") (class "Default")
      (node (ref "C34") (pin "2") (pinfunction "2_2") (pintype "passive"))
      (node (ref "U3") (pin "49") (pinfunction "PD10/XT32KI_49") (pintype "passive"))
      (node (ref "Y1") (pin "1") (pinfunction "P1_1") (pintype "passive"))
    )
    (net (code "42") (name "GND") (class "Default")
      (node (ref "C15") (pin "2") (pinfunction "2_2") (pintype "passive"))
      (node (ref "C16") (pin "1") (pinfunction "1_1") (pintype "passive"))
      (node (ref "C17") (pin "1") (pinfunction "1_1") (pintype "passive"))
      (node (ref "C18") (pin "1") (pinfunction "1_1") (pintype "passive"))
      (node (ref "C19") (pin "1") (pinfunction "1_1") (pintype "passive"))
      (node (ref "C20") (pin "1") (pinfunction "1_1") (pintype "passive"))
      (node (ref "C21") (pin "1") (pinfunction "1_1") (pintype "passive"))
      (node (ref "C22") (pin "1") (pinfunction "1_1") (pintype "passive"))
      (node (ref "C23") (pin "1") (pinfunction "1_1") (pintype "passive"))
      (node (ref "C24") (pin "1") (pinfunction "1_1") (pintype "passive"))
      (node (ref "C25") (pin "1") (pinfunction "1_1") (pintype "passive"))
      (node (ref "C26") (pin "1") (pinfunction "1_1") (pintype "passive"))
      (node (ref "C27") (pin "1") (pinfunction "1_1") (pintype "passive"))
      (node (ref "C29") (pin "1") (pinfunction "1_1") (pintype "passive"))
      (node (ref "C30") (pin "1") (pinfunction "1_1") (pintype "passive"))
      (node (ref "C31") (pin "1") (pinfunction "1_1") (pintype "passive"))
      (node (ref "C32") (pin "1") (pinfunction "1_1") (pintype "passive"))
      (node (ref "C33") (pin "1") (pinfunction "1_1") (pintype "passive"))
      (node (ref "C34") (pin "1") (pinfunction "1_1") (pintype "passive"))
      (node (ref "C35") (pin "1") (pinfunction "1_1") (pintype "passive"))
      (node (ref "C36") (pin "2") (pinfunction "2_2") (pintype "passive"))
      (node (ref "C37") (pin "1") (pinfunction "1_1") (pintype "passive"))
      (node (ref "C38") (pin "1") (pinfunction "1_1") (pintype "passive"))
      (node (ref "C39") (pin "1") (pinfunction "1_1") (pintype "passive"))
      (node (ref "C40") (pin "1") (pinfunction "1_1") (pintype "passive"))
      (node (ref "C41") (pin "1") (pinfunction "1_1") (pintype "passive"))
      (node (ref "C42") (pin "1") (pinfunction "1_1") (pintype "passive"))
      (node (ref "C43") (pin "2") (pinfunction "2_2") (pintype "passive"))
      (node (ref "C44") (pin "2") (pinfunction "2_2") (pintype "passive"))
      (node (ref "C47") (pin "2") (pinfunction "2_2") (pintype "passive"))
      (node (ref "C48") (pin "1") (pinfunction "1_1") (pintype "passive"))
      (node (ref "C49") (pin "1") (pinfunction "1_1") (pintype "passive"))
      (node (ref "C51") (pin "1") (pinfunction "1_1") (pintype "passive"))
      (node (ref "C52") (pin "2") (pinfunction "2_2") (pintype "passive"))
      (node (ref "C53") (pin "2") (pinfunction "2_2") (pintype "passive"))
      (node (ref "C54") (pin "1") (pinfunction "1_1") (pintype "passive"))
      (node (ref "C55") (pin "2") (pinfunction "2_2") (pintype "passive"))
      (node (ref "C56") (pin "2") (pinfunction "2_2") (pintype "passive"))
      (node (ref "C57") (pin "2") (pinfunction "2_2") (pintype "passive"))
      (node (ref "C58") (pin "2") (pinfunction "2_2") (pintype "passive"))
      (node (ref "C59") (pin "2") (pinfunction "2_2") (pintype "passive"))
      (node (ref "C60") (pin "1") (pinfunction "1_1") (pintype "passive"))
      (node (ref "C61") (pin "1") (pinfunction "1_1") (pintype "passive"))
      (node (ref "C62") (pin "2") (pinfunction "2_2") (pintype "passive"))
      (node (ref "D3") (pin "1") (pinfunction "A_1") (pintype "passive"))
      (node (ref "J1") (pin "2") (pinfunction "2_2") (pintype "passive"))
      (node (ref "J2") (pin "1") (pinfunction "1_1") (pintype "passive"))
      (node (ref "J3") (pin "2") (pinfunction "2_2") (pintype "passive"))
      (node (ref "J4") (pin "3") (pinfunction "3_3") (pintype "passive"))
      (node (ref "J5") (pin "3") (pinfunction "3_3") (pintype "passive"))
      (node (ref "P1") (pin "2") (pinfunction "2_2") (pintype "passive"))
      (node (ref "Q10") (pin "2") (pinfunction "E_2") (pintype "passive"))
      (node (ref "Q13") (pin "2") (pinfunction "E_2") (pintype "passive"))
      (node (ref "Q6") (pin "2") (pinfunction "E_2") (pintype "passive"))
      (node (ref "Q9") (pin "3") (pinfunction "C_3") (pintype "passive"))
      (node (ref "R24") (pin "2") (pinfunction "2_2") (pintype "passive"))
      (node (ref "R27") (pin "1") (pinfunction "1_1") (pintype "passive"))
      (node (ref "R28") (pin "1") (pinfunction "1_1") (pintype "passive"))
      (node (ref "R36") (pin "1") (pinfunction "1_1") (pintype "passive"))
      (node (ref "R37") (pin "1") (pinfunction "1_1") (pintype "passive"))
      (node (ref "R44") (pin "1") (pinfunction "1_1") (pintype "passive"))
      (node (ref "U10") (pin "2") (pinfunction "2_2") (pintype "passive"))
      (node (ref "U11") (pin "3") (pinfunction "GND_3") (pintype "passive"))
      (node (ref "U3") (pin "33") (pinfunction "VSS_33") (pintype "passive"))
      (node (ref "U3") (pin "51") (pinfunction "VSS_51") (pintype "passive"))
      (node (ref "U3") (pin "53") (pinfunction "VREFN_53") (pintype "passive"))
      (node (ref "U4") (pin "1") (pinfunction "GND_1") (pintype "passive"))
      (node (ref "U5") (pin "2") (pinfunction "GND_2") (pintype "passive"))
      (node (ref "U6") (pin "9") (pinfunction "Pad_9") (pintype "passive"))
      (node (ref "U7") (pin "4") (pinfunction "VSS_4") (pintype "passive"))
      (node (ref "U8") (pin "2") (pinfunction "GND_2") (pintype "passive"))
      (node (ref "U8") (pin "6") (pinfunction "TOB_6") (pintype "passive"))
      (node (ref "U9") (pin "2") (pinfunction "2_2") (pintype "passive"))
    )
    (net (code "43") (name "KEY_VCC") (class "Default")
      (node (ref "R41") (pin "2") (pinfunction "2_2") (pintype "passive"))
      (node (ref "U3") (pin "2") (pinfunction "COMP1_INP3/ADC_IN6/LPUART0_RX/UART0_RX/PA13_2") (pintype "passive"))
    )
    (net (code "44") (name "Net-(C60-Pad2)") (class "Default")
      (node (ref "C60") (pin "2") (pinfunction "2_2") (pintype "passive"))
      (node (ref "J3") (pin "5") (pinfunction "5_5") (pintype "passive"))
      (node (ref "R30") (pin "2") (pinfunction "2_2") (pintype "passive"))
    )
    (net (code "45") (name "Net-(D4-K)") (class "Default")
      (node (ref "D4") (pin "2") (pinfunction "K_2") (pintype "passive"))
      (node (ref "R29") (pin "1") (pinfunction "1_1") (pintype "passive"))
    )
    (net (code "46") (name "Net-(D6-A)") (class "Default")
      (node (ref "D6") (pin "1") (pinfunction "A_1") (pintype "passive"))
      (node (ref "R42") (pin "2") (pinfunction "2_2") (pintype "passive"))
    )
    (net (code "47") (name "Net-(D6-K)") (class "Default")
      (node (ref "D6") (pin "2") (pinfunction "K_2") (pintype "passive"))
      (node (ref "D7") (pin "1") (pinfunction "A_1") (pintype "passive"))
      (node (ref "Q7") (pin "3") (pinfunction "C_3") (pintype "passive"))
      (node (ref "R35") (pin "2") (pinfunction "2_2") (pintype "passive"))
      (node (ref "R39") (pin "2") (pinfunction "2_2") (pintype "passive"))
    )
    (net (code "48") (name "Net-(D7-K)") (class "Default")
      (node (ref "D7") (pin "2") (pinfunction "K_2") (pintype "passive"))
      (node (ref "R43") (pin "2") (pinfunction "2_2") (pintype "passive"))
    )
    (net (code "49") (name "Net-(J4-Pad4)") (class "Default")
      (node (ref "J4") (pin "4") (pinfunction "4_4") (pintype "passive"))
      (node (ref "R48") (pin "2") (pinfunction "2_2") (pintype "passive"))
    )
    (net (code "50") (name "Net-(J4-Pad5)") (class "Default")
      (node (ref "J4") (pin "5") (pinfunction "5_5") (pintype "passive"))
      (node (ref "R49") (pin "2") (pinfunction "2_2") (pintype "passive"))
    )
    (net (code "51") (name "Net-(J5-Pad2)") (class "Default")
      (node (ref "J5") (pin "2") (pinfunction "2_2") (pintype "passive"))
      (node (ref "R45") (pin "2") (pinfunction "2_2") (pintype "passive"))
    )
    (net (code "52") (name "Net-(J5-Pad4)") (class "Default")
      (node (ref "J5") (pin "4") (pinfunction "4_4") (pintype "passive"))
      (node (ref "R46") (pin "2") (pinfunction "2_2") (pintype "passive"))
    )
    (net (code "53") (name "Net-(J5-Pad5)") (class "Default")
      (node (ref "J5") (pin "5") (pinfunction "5_5") (pintype "passive"))
      (node (ref "R47") (pin "2") (pinfunction "2_2") (pintype "passive"))
    )
    (net (code "54") (name "Net-(KT1-Pad1)") (class "Default")
      (node (ref "KT1") (pin "1") (pinfunction "1_1") (pintype "passive"))
      (node (ref "R50") (pin "1") (pinfunction "1_1") (pintype "passive"))
    )
    (net (code "55") (name "Net-(Q5-B)") (class "Default")
      (node (ref "Q5") (pin "1") (pinfunction "B_1") (pintype "passive"))
      (node (ref "R20") (pin "2") (pinfunction "2_2") (pintype "passive"))
    )
    (net (code "56") (name "Net-(Q5-C)") (class "Default")
      (node (ref "Q5") (pin "3") (pinfunction "C_3") (pintype "passive"))
      (node (ref "R22") (pin "1") (pinfunction "1_1") (pintype "passive"))
    )
    (net (code "57") (name "Net-(Q6-B)") (class "Default")
      (node (ref "Q6") (pin "1") (pinfunction "B_1") (pintype "passive"))
      (node (ref "R21") (pin "2") (pinfunction "2_2") (pintype "passive"))
    )
    (net (code "58") (name "Net-(Q6-C)") (class "Default")
      (node (ref "Q6") (pin "3") (pinfunction "C_3") (pintype "passive"))
      (node (ref "R19") (pin "1") (pinfunction "1_1") (pintype "passive"))
      (node (ref "R20") (pin "1") (pinfunction "1_1") (pintype "passive"))
    )
    (net (code "59") (name "Net-(Q7-B)") (class "Default")
      (node (ref "Q7") (pin "1") (pinfunction "B_1") (pintype "passive"))
      (node (ref "R33") (pin "2") (pinfunction "2_2") (pintype "passive"))
    )
    (net (code "60") (name "Net-(Q8-B)") (class "Default")
      (node (ref "Q8") (pin "1") (pinfunction "B_1") (pintype "passive"))
      (node (ref "R38") (pin "2") (pinfunction "2_2") (pintype "passive"))
    )
    (net (code "61") (name "Net-(Q9-B)") (class "Default")
      (node (ref "Q9") (pin "1") (pinfunction "B_1") (pintype "passive"))
      (node (ref "R40") (pin "2") (pinfunction "2_2") (pintype "passive"))
    )
    (net (code "62") (name "Net-(Q9-E)") (class "Default")
      (node (ref "Q9") (pin "2") (pinfunction "E_2") (pintype "passive"))
      (node (ref "R43") (pin "1") (pinfunction "1_1") (pintype "passive"))
    )
    (net (code "63") (name "Net-(Q10-B)") (class "Default")
      (node (ref "C44") (pin "1") (pinfunction "1_1") (pintype "passive"))
      (node (ref "Q10") (pin "1") (pinfunction "B_1") (pintype "passive"))
      (node (ref "R42") (pin "1") (pinfunction "1_1") (pintype "passive"))
      (node (ref "R44") (pin "2") (pinfunction "2_2") (pintype "passive"))
    )
    (net (code "64") (name "Net-(Q12-G)") (class "Default")
      (node (ref "Q12") (pin "1") (pinfunction "G_1") (pintype "passive"))
      (node (ref "R23") (pin "1") (pinfunction "1_1") (pintype "passive"))
      (node (ref "R31") (pin "2") (pinfunction "2_2") (pintype "passive"))
    )
    (net (code "65") (name "Net-(Q13-B)") (class "Default")
      (node (ref "Q13") (pin "1") (pinfunction "B_1") (pintype "passive"))
      (node (ref "R32") (pin "1") (pinfunction "1_1") (pintype "passive"))
    )
    (net (code "66") (name "Net-(Q13-C)") (class "Default")
      (node (ref "Q13") (pin "3") (pinfunction "C_3") (pintype "passive"))
      (node (ref "R31") (pin "1") (pinfunction "1_1") (pintype "passive"))
    )
    (net (code "67") (name "Net-(Q14-D)") (class "Default")
      (node (ref "C39") (pin "2") (pinfunction "2_2") (pintype "passive"))
      (node (ref "C61") (pin "2") (pinfunction "2_2") (pintype "passive"))
      (node (ref "C62") (pin "1") (pinfunction "1_1") (pintype "passive"))
      (node (ref "Q14") (pin "3") (pinfunction "D_3") (pintype "passive"))
      (node (ref "U8") (pin "4") (pinfunction "AHLB_4") (pintype "passive"))
      (node (ref "U8") (pin "5") (pinfunction "VCC_5") (pintype "passive"))
    )
    (net (code "68") (name "Net-(Q14-G)") (class "Default")
      (node (ref "Q14") (pin "1") (pinfunction "G_1") (pintype "passive"))
      (node (ref "R34") (pin "1") (pinfunction "1_1") (pintype "passive"))
      (node (ref "R41") (pin "1") (pinfunction "1_1") (pintype "passive"))
    )
    (net (code "69") (name "Net-(U3-VDD15)") (class "Default")
      (node (ref "C23") (pin "2") (pinfunction "2_2") (pintype "passive"))
      (node (ref "U3") (pin "50") (pinfunction "VDD15_50") (pintype "passive"))
    )
    (net (code "70") (name "Net-(U4-Vin)") (class "Default")
      (node (ref "C15") (pin "1") (pinfunction "1_1") (pintype "passive"))
      (node (ref "D1") (pin "2") (pinfunction "2_2") (pintype "passive"))
      (node (ref "U4") (pin "2") (pinfunction "Vin_2") (pintype "passive"))
    )
    (net (code "71") (name "Net-(U5-EN)") (class "Default")
      (node (ref "C32") (pin "2") (pinfunction "2_2") (pintype "passive"))
      (node (ref "R26") (pin "2") (pinfunction "2_2") (pintype "passive"))
      (node (ref "R27") (pin "2") (pinfunction "2_2") (pintype "passive"))
      (node (ref "U5") (pin "4") (pinfunction "EN_4") (pintype "passive"))
    )
    (net (code "72") (name "Net-(U5-FB)") (class "Default")
      (node (ref "C28") (pin "1") (pinfunction "1_1") (pintype "passive"))
      (node (ref "R25") (pin "1") (pinfunction "1_1") (pintype "passive"))
      (node (ref "R28") (pin "2") (pinfunction "2_2") (pintype "passive"))
      (node (ref "U5") (pin "3") (pinfunction "FB_3") (pintype "passive"))
    )
    (net (code "73") (name "Net-(U5-LX)") (class "Default")
      (node (ref "L1") (pin "2") (pinfunction "2_2") (pintype "passive"))
      (node (ref "U5") (pin "1") (pinfunction "LX_1") (pintype "passive"))
    )
    (net (code "74") (name "Net-(U8-KEY)") (class "Default")
      (node (ref "C40") (pin "2") (pinfunction "2_2") (pintype "passive"))
      (node (ref "R50") (pin "2") (pinfunction "2_2") (pintype "passive"))
      (node (ref "U8") (pin "3") (pinfunction "KEY_3") (pintype "passive"))
    )
    (net (code "75") (name "VBAT") (class "Default")
      (node (ref "D1") (pin "1") (pinfunction "1_1") (pintype "passive"))
      (node (ref "D2") (pin "1") (pinfunction "1_1") (pintype "passive"))
      (node (ref "D3") (pin "2") (pinfunction "K_2") (pintype "passive"))
      (node (ref "J1") (pin "1") (pinfunction "1_1") (pintype "passive"))
      (node (ref "P1") (pin "1") (pinfunction "1_1") (pintype "passive"))
      (node (ref "Q5") (pin "2") (pinfunction "E_2") (pintype "passive"))
      (node (ref "R19") (pin "2") (pinfunction "2_2") (pintype "passive"))
    )
    (net (code "76") (name "VCC") (class "Default")
      (node (ref "C16") (pin "2") (pinfunction "2_2") (pintype "passive"))
      (node (ref "C17") (pin "2") (pinfunction "2_2") (pintype "passive"))
      (node (ref "C20") (pin "2") (pinfunction "2_2") (pintype "passive"))
      (node (ref "C21") (pin "2") (pinfunction "2_2") (pintype "passive"))
      (node (ref "C24") (pin "2") (pinfunction "2_2") (pintype "passive"))
      (node (ref "C25") (pin "2") (pinfunction "2_2") (pintype "passive"))
      (node (ref "C35") (pin "2") (pinfunction "2_2") (pintype "passive"))
      (node (ref "C41") (pin "2") (pinfunction "2_2") (pintype "passive"))
      (node (ref "C42") (pin "2") (pinfunction "2_2") (pintype "passive"))
      (node (ref "C49") (pin "2") (pinfunction "2_2") (pintype "passive"))
      (node (ref "C51") (pin "2") (pinfunction "2_2") (pintype "passive"))
      (node (ref "C54") (pin "2") (pinfunction "2_2") (pintype "passive"))
      (node (ref "C59") (pin "1") (pinfunction "1_1") (pintype "passive"))
      (node (ref "D4") (pin "1") (pinfunction "A_1") (pintype "passive"))
      (node (ref "J3") (pin "1") (pinfunction "1_1") (pintype "passive"))
      (node (ref "J5") (pin "1") (pinfunction "1_1") (pintype "passive"))
      (node (ref "Q14") (pin "2") (pinfunction "S_2") (pintype "passive"))
      (node (ref "Q7") (pin "2") (pinfunction "E_2") (pintype "passive"))
      (node (ref "Q8") (pin "2") (pinfunction "E_2") (pintype "passive"))
      (node (ref "R1") (pin "2") (pinfunction "2_2") (pintype "passive"))
      (node (ref "R18") (pin "2") (pinfunction "2_2") (pintype "passive"))
      (node (ref "R2") (pin "2") (pinfunction "2_2") (pintype "passive"))
      (node (ref "R34") (pin "2") (pinfunction "2_2") (pintype "passive"))
      (node (ref "U10") (pin "1") (pinfunction "1_1") (pintype "passive"))
      (node (ref "U11") (pin "1") (pinfunction "VDD_1") (pintype "passive"))
      (node (ref "U3") (pin "34") (pinfunction "VDD_34") (pintype "passive"))
      (node (ref "U3") (pin "52") (pinfunction "VDD_52") (pintype "passive"))
      (node (ref "U3") (pin "54") (pinfunction "VREFP_54") (pintype "passive"))
      (node (ref "U4") (pin "3") (pinfunction "Vout_3") (pintype "passive"))
      (node (ref "U6") (pin "8") (pinfunction "VCC_8") (pintype "passive"))
      (node (ref "U9") (pin "1") (pinfunction "1_1") (pintype "passive"))
    )
    (net (code "77") (name "VCC_M") (class "Default")
      (node (ref "C19") (pin "2") (pinfunction "2_2") (pintype "passive"))
      (node (ref "C26") (pin "2") (pinfunction "2_2") (pintype "passive"))
      (node (ref "C27") (pin "2") (pinfunction "2_2") (pintype "passive"))
      (node (ref "C36") (pin "1") (pinfunction "1_1") (pintype "passive"))
      (node (ref "D2") (pin "2") (pinfunction "2_2") (pintype "passive"))
      (node (ref "L1") (pin "1") (pinfunction "1_1") (pintype "passive"))
      (node (ref "Q12") (pin "2") (pinfunction "S_2") (pintype "passive"))
      (node (ref "R23") (pin "2") (pinfunction "2_2") (pintype "passive"))
      (node (ref "U5") (pin "6") (pinfunction "IN_6") (pintype "passive"))
      (node (ref "U6") (pin "1") (pinfunction "VM_1") (pintype "passive"))
    )
    (net (code "78") (name "unconnected-(U3-ADC_IN4{slash}UART5_TX{slash}SEG23{slash}PD1-Pad57)") (class "Default")
      (node (ref "U3") (pin "57") (pinfunction "ADC_IN4/UART5_TX/SEG23/PD1_57") (pintype "passive+no_connect"))
    )
    (net (code "79") (name "unconnected-(U3-ATIM_BRK2{slash}ANATST{slash}PD6(WKUP7)-Pad62)") (class "Default")
      (node (ref "U3") (pin "62") (pinfunction "ATIM_BRK2/ANATST/PD6(WKUP7)_62") (pintype "passive"))
    )
    (net (code "80") (name "unconnected-(U3-COMP2_INN1{slash}GPT1_CH3{slash}COM4{slash}SEG28{slash}PA4-Pad9)") (class "Default")
      (node (ref "U3") (pin "9") (pinfunction "COMP2_INN1/GPT1_CH3/COM4/SEG28/PA4_9") (pintype "passive"))
    )
    (net (code "81") (name "unconnected-(U3-PB3{slash}UART4_TX{slash}ATIM_CH2N-Pad21)") (class "Default")
      (node (ref "U3") (pin "21") (pinfunction "PB3/UART4_TX/ATIM_CH2N_21") (pintype "passive"))
    )
    (net (code "82") (name "unconnected-(U3-PB6{slash}SEG5{slash}ATIM_CH3-Pad24)") (class "Default")
      (node (ref "U3") (pin "24") (pinfunction "PB6/SEG5/ATIM_CH3_24") (pintype "passive"))
    )
    (net (code "83") (name "unconnected-(U3-PB8{slash}SEG7{slash}SPI1_SSN{slash}ATIM_CH3N-Pad26)") (class "Default")
      (node (ref "U3") (pin "26") (pinfunction "PB8/SEG7/SPI1_SSN/ATIM_CH3N_26") (pintype "passive"))
    )
    (net (code "84") (name "unconnected-(U3-PB9{slash}SEG8{slash}SPI1_SCK{slash}GPT0_ETR{slash}ANATST-Pad27)") (class "Default")
      (node (ref "U3") (pin "27") (pinfunction "PB9/SEG8/SPI1_SCK/GPT0_ETR/ANATST_27") (pintype "passive"))
    )
    (net (code "85") (name "unconnected-(U3-PB10{slash}SEG9{slash}SPI1_MISO{slash}GPT0_CH1-Pad28)") (class "Default")
      (node (ref "U3") (pin "28") (pinfunction "PB10/SEG9/SPI1_MISO/GPT0_CH1_28") (pintype "passive"))
    )
    (net (code "86") (name "unconnected-(U3-PC0{slash}GPT1_CH1{slash}I2CSMB_SCL-Pad35)") (class "Default")
      (node (ref "U3") (pin "35") (pinfunction "PC0/GPT1_CH1/I2CSMB_SCL_35") (pintype "passive"))
    )
    (net (code "87") (name "unconnected-(U3-PC1{slash}GPT1_CH2{slash}I2CSMB_SDA-Pad36)") (class "Default")
      (node (ref "U3") (pin "36") (pinfunction "PC1/GPT1_CH2/I2CSMB_SDA_36") (pintype "passive"))
    )
    (net (code "88") (name "unconnected-(U3-PC2{slash}XTHIN{slash}UART1_RX{slash}LPUART1_RX-Pad37)") (class "Default")
      (node (ref "U3") (pin "37") (pinfunction "PC2/XTHIN/UART1_RX/LPUART1_RX_37") (pintype "passive+no_connect"))
    )
    (net (code "89") (name "unconnected-(U3-PC3{slash}XTHOUT{slash}UART1_TX{slash}LPUART1_TX-Pad38)") (class "Default")
      (node (ref "U3") (pin "38") (pinfunction "PC3/XTHOUT/UART1_TX/LPUART1_TX_38") (pintype "passive+no_connect"))
    )
    (net (code "90") (name "unconnected-(U3-PC5{slash}SEG14{slash}UART5_TX{slash}SCL-Pad40)") (class "Default")
      (node (ref "U3") (pin "40") (pinfunction "PC5/SEG14/UART5_TX/SCL_40") (pintype "passive+no_connect"))
    )
    (net (code "91") (name "unconnected-(U3-PC6(WKUP4){slash}SEG15{slash}ADC_IN11{slash}GPT1_ETR{slash}I2CSMB_ALERT-Pad41)") (class "Default")
      (node (ref "U3") (pin "41") (pinfunction "PC6(WKUP4)/SEG15/ADC_IN11/GPT1_ETR/I2CSMB_ALERT_41") (pintype "passive"))
    )
    (net (code "92") (name "unconnected-(U3-PC8{slash}SEG17{slash}ADC_IN9{slash}SPI2_SCK-Pad43)") (class "Default")
      (node (ref "U3") (pin "43") (pinfunction "PC8/SEG17/ADC_IN9/SPI2_SCK_43") (pintype "passive"))
    )
    (net (code "93") (name "unconnected-(U3-PC12{slash}SEG21{slash}U7816IO{slash}GPT0_CH4-Pad47)") (class "Default")
      (node (ref "U3") (pin "47") (pinfunction "PC12/SEG21/U7816IO/GPT0_CH4_47") (pintype "passive"))
    )
    (net (code "94") (name "unconnected-(U3-SCL{slash}PA11-Pad16)") (class "Default")
      (node (ref "U3") (pin "16") (pinfunction "SCL/PA11_16") (pintype "passive"))
    )
  )
)
